# unity_amplifier.net
KiCad netlist of a schematic drawn in Altium Designer
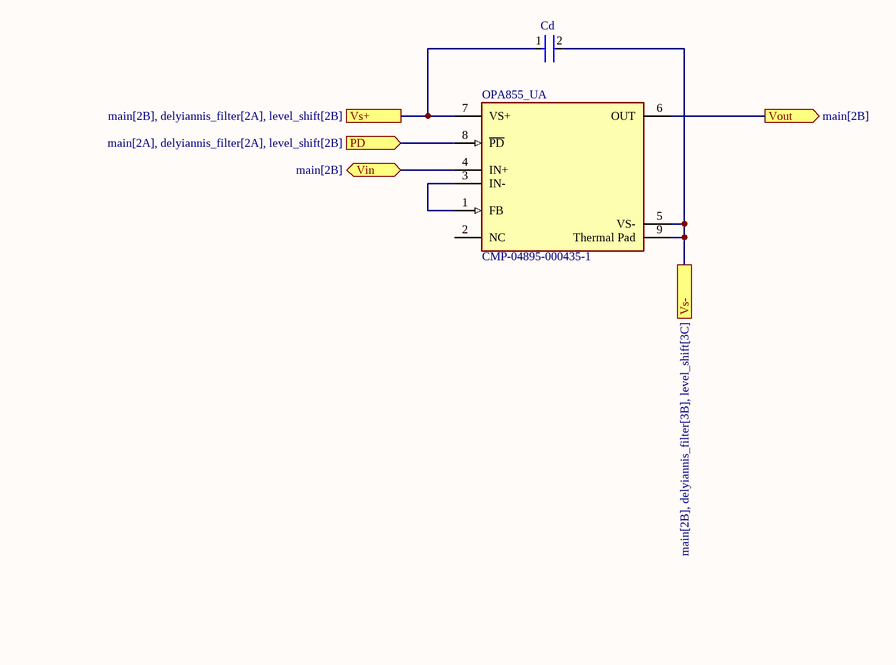
[diagram p0: unity_amplifier.SchDoc]

(export (version "E")
  (design (tool "Eeschema 10.0.6"))
  (components
    (comp (ref "Cd")
      (value "C0402C104K4RACTU")
      (footprint "FP-C0402-BB-MFG")
      (description "CAP CER 0.1UF 16V X7R 0402")
      (fields
        (field (name "TOLERANCE") "0.1")
        (field (name "OCTOPART") "https://octopart.com/c0402c104k4ractu-kemet-94158")
      )
      (libsource (lib "Altium Content Vault") (part "b4654b650e69147ec39a6b967a45e02"))
    )
    (comp (ref "OPA855_UA")
      (value "CMP-04895-000435-1")
      (footprint "FP-DSG0008A-MFG")
      (description "IC OPAMP GP 1 CIRCUIT 8WSON")
      (libsource (lib "kevin kim") (part "CMP-04895-000435-1"))
    )
  )
  (nets
    (net (code "1") (name "/PD") (class "Default")
      (node (ref "OPA855_UA") (pin "8") (pinfunction "~{PD}_8") (pintype "input"))
    )
    (net (code "2") (name "/Vin") (class "Default")
      (node (ref "OPA855_UA") (pin "4") (pinfunction "IN+_4") (pintype "tri_state"))
    )
    (net (code "3") (name "/Vout") (class "Default")
      (node (ref "OPA855_UA") (pin "6") (pinfunction "OUT_6") (pintype "passive"))
    )
    (net (code "4") (name "/Vs+") (class "Default")
      (node (ref "Cd") (pin "1") (pinfunction "1_1") (pintype "passive"))
      (node (ref "OPA855_UA") (pin "7") (pinfunction "VS+_7") (pintype "power_in"))
    )
    (net (code "5") (name "/Vs-") (class "Default")
      (node (ref "Cd") (pin "2") (pinfunction "2_2") (pintype "passive"))
      (node (ref "OPA855_UA") (pin "5") (pinfunction "VS-_5") (pintype "power_in"))
      (node (ref "OPA855_UA") (pin "9") (pinfunction "Thermal_Pad_9") (pintype "passive"))
    )
    (net (code "6") (name "Net-(OPA855_UA-FB)") (class "Default")
      (node (ref "OPA855_UA") (pin "1") (pinfunction "FB_1") (pintype "input"))
      (node (ref "OPA855_UA") (pin "3") (pinfunction "IN-_3") (pintype "tri_state"))
    )
    (net (code "7") (name "unconnected-(OPA855_UA-NC-Pad2)") (class "Default")
      (node (ref "OPA855_UA") (pin "2") (pinfunction "NC_2") (pintype "passive"))
    )
  )
)
